# InterfazRS232Radio.net
KiCad netlist of a schematic drawn in Altium Designer
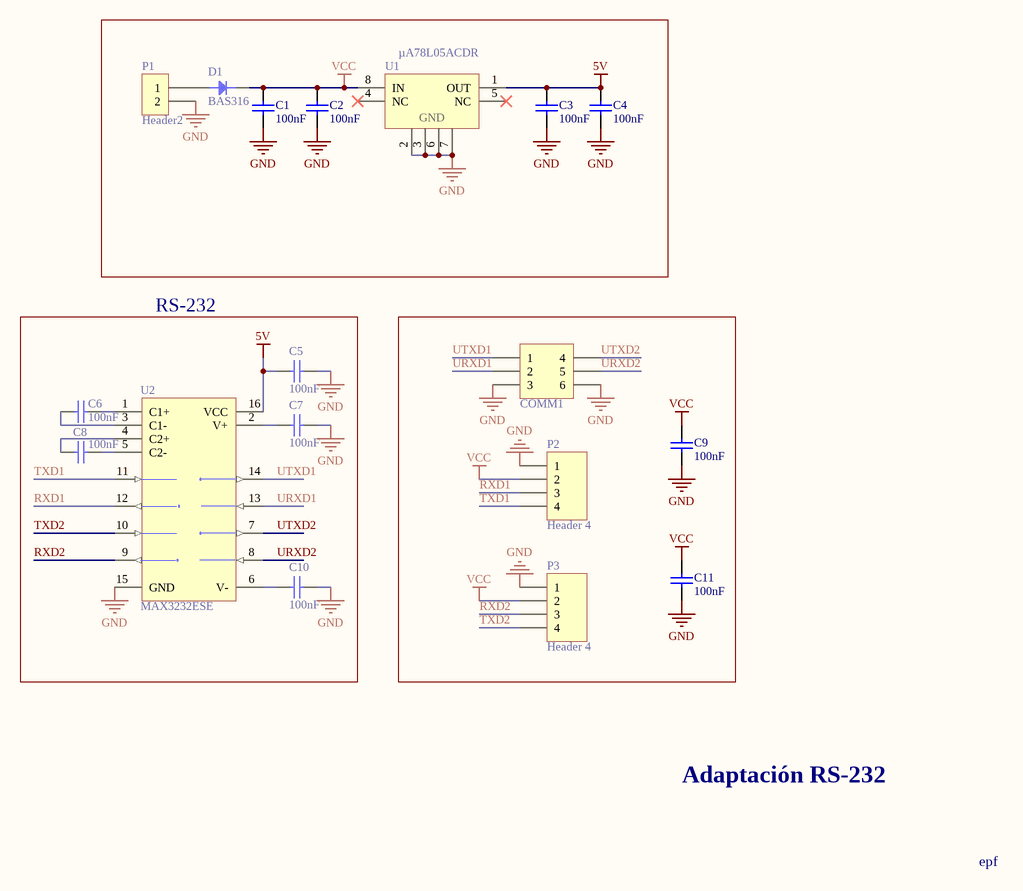
[diagram p0: InterfazRS232Radio.SchDoc]

(export (version "E")
  (design (tool "Eeschema 10.0.6"))
  (components
    (comp (ref "C1")
      (value "100nF")
      (footprint "0805_CAP")
      (fields (field (name "Comment") "Capacitor"))
      (libsource (lib "epf") (part "Cap"))
    )
    (comp (ref "C2")
      (value "100nF")
      (footprint "0805_CAP")
      (fields (field (name "Comment") "Capacitor"))
      (libsource (lib "epf") (part "Cap"))
    )
    (comp (ref "C3")
      (value "100nF")
      (footprint "0805_CAP")
      (fields (field (name "Comment") "Capacitor"))
      (libsource (lib "epf") (part "Cap"))
    )
    (comp (ref "C4")
      (value "100nF")
      (footprint "0805_CAP")
      (fields (field (name "Comment") "Capacitor"))
      (libsource (lib "epf") (part "Cap"))
    )
    (comp (ref "C5")
      (value "100nF")
      (footprint "0805_CAP")
      (fields (field (name "Comment") "Capacitor"))
      (libsource (lib "epf") (part "Cap"))
    )
    (comp (ref "C6")
      (value "100nF")
      (footprint "0805_CAP")
      (fields (field (name "Comment") "Capacitor"))
      (libsource (lib "epf") (part "Cap"))
    )
    (comp (ref "C7")
      (value "100nF")
      (footprint "0805_CAP")
      (fields (field (name "Comment") "Capacitor"))
      (libsource (lib "epf") (part "Cap"))
    )
    (comp (ref "C8")
      (value "100nF")
      (footprint "0805_CAP")
      (fields (field (name "Comment") "Capacitor"))
      (libsource (lib "epf") (part "Cap"))
    )
    (comp (ref "C9")
      (value "100nF")
      (footprint "0805_CAP")
      (fields (field (name "Comment") "Capacitor"))
      (libsource (lib "epf") (part "Cap"))
    )
    (comp (ref "C10")
      (value "100nF")
      (footprint "0805_CAP")
      (fields (field (name "Comment") "Capacitor"))
      (libsource (lib "epf") (part "Cap"))
    )
    (comp (ref "C11")
      (value "100nF")
      (footprint "0805_CAP")
      (fields (field (name "Comment") "Capacitor"))
      (libsource (lib "epf") (part "Cap"))
    )
    (comp (ref "COMM1")
      (value "AP_COMM")
      (footprint "HDR2X3_CEN")
      (description "Header, 3-Pin, Dual row")
      (fields (field (name "PUBLISHER") "Altium Limited"))
      (libsource (lib "epf") (part "AP_COMM"))
    )
    (comp (ref "D1") (value "BAS316") (footprint "SOD-323") (libsource (lib "epf") (part "BAS316")))
    (comp (ref "P1") (value "Header2") (footprint "Header2Macho") (libsource (lib "epf") (part "Header2")))
    (comp (ref "P2")
      (value "Header 4")
      (footprint "HDR1X4")
      (description "Header, 4-Pin")
      (fields (field (name "PUBLISHER") "Altium Limited"))
      (libsource (lib "Miscellaneous Connectors") (part "Header 4"))
    )
    (comp (ref "P3")
      (value "Header 4")
      (footprint "HDR1X4")
      (description "Header, 4-Pin")
      (fields (field (name "PUBLISHER") "Altium Limited"))
      (libsource (lib "Miscellaneous Connectors") (part "Header 4"))
    )
    (comp (ref "U1")
      (value "µA78L05ACDR")
      (footprint "D008_N")
      (description "Positive-Voltage Regulator")
      (fields (field (name "PUBLISHER") "Altium Limited"))
      (libsource (lib "TI Power Mgt Voltage Regulator") (part "µA78L05ACDR"))
    )
    (comp (ref "U2")
      (value "MAX3232ESE")
      (footprint "SOIC127P602-16BN")
      (libsource (lib "epf") (part "MAX3232ESE+"))
    )
  )
  (nets
    (net (code "1") (name "/RXD1") (class "Default")
      (node (ref "P2") (pin "3") (pinfunction "3_3") (pintype "passive"))
      (node (ref "U2") (pin "12") (pinfunction "R1OUT_12") (pintype "output"))
    )
    (net (code "2") (name "/RXD2") (class "Default")
      (node (ref "P3") (pin "3") (pinfunction "3_3") (pintype "passive"))
      (node (ref "U2") (pin "9") (pinfunction "R2OUT_9") (pintype "output"))
    )
    (net (code "3") (name "/TXD1") (class "Default")
      (node (ref "P2") (pin "4") (pinfunction "4_4") (pintype "passive"))
      (node (ref "U2") (pin "11") (pinfunction "T1IN_11") (pintype "input"))
    )
    (net (code "4") (name "/TXD2") (class "Default")
      (node (ref "P3") (pin "4") (pinfunction "4_4") (pintype "passive"))
      (node (ref "U2") (pin "10") (pinfunction "T2IN_10") (pintype "input"))
    )
    (net (code "5") (name "/URXD1") (class "Default")
      (node (ref "COMM1") (pin "2") (pinfunction "2_2") (pintype "passive"))
      (node (ref "U2") (pin "13") (pinfunction "R1IN_13") (pintype "input"))
    )
    (net (code "6") (name "/URXD2") (class "Default")
      (node (ref "COMM1") (pin "5") (pinfunction "5_5") (pintype "passive"))
      (node (ref "U2") (pin "8") (pinfunction "R2IN_8") (pintype "input"))
    )
    (net (code "7") (name "/UTXD1") (class "Default")
      (node (ref "COMM1") (pin "1") (pinfunction "1_1") (pintype "passive"))
      (node (ref "U2") (pin "14") (pinfunction "T1OUT_14") (pintype "output"))
    )
    (net (code "8") (name "/UTXD2") (class "Default")
      (node (ref "COMM1") (pin "4") (pinfunction "4_4") (pintype "passive"))
      (node (ref "U2") (pin "7") (pinfunction "T2OUT_7") (pintype "output"))
    )
    (net (code "9") (name "5V") (class "Default")
      (node (ref "C3") (pin "1") (pinfunction "1_1") (pintype "passive"))
      (node (ref "C4") (pin "1") (pinfunction "1_1") (pintype "passive"))
      (node (ref "C5") (pin "2") (pinfunction "2_2") (pintype "passive"))
      (node (ref "U1") (pin "1") (pinfunction "OUT_1") (pintype "power_in"))
      (node (ref "U2") (pin "16") (pinfunction "VCC_16") (pintype "power_in"))
    )
    (net (code "10") (name "GND") (class "Default")
      (node (ref "C1") (pin "2") (pinfunction "2_2") (pintype "passive"))
      (node (ref "C10") (pin "1") (pinfunction "1_1") (pintype "passive"))
      (node (ref "C11") (pin "2") (pinfunction "2_2") (pintype "passive"))
      (node (ref "C2") (pin "2") (pinfunction "2_2") (pintype "passive"))
      (node (ref "C3") (pin "2") (pinfunction "2_2") (pintype "passive"))
      (node (ref "C4") (pin "2") (pinfunction "2_2") (pintype "passive"))
      (node (ref "C5") (pin "1") (pinfunction "1_1") (pintype "passive"))
      (node (ref "C7") (pin "1") (pinfunction "1_1") (pintype "passive"))
      (node (ref "C9") (pin "2") (pinfunction "2_2") (pintype "passive"))
      (node (ref "COMM1") (pin "3") (pinfunction "3_3") (pintype "passive"))
      (node (ref "COMM1") (pin "6") (pinfunction "6_6") (pintype "passive"))
      (node (ref "P1") (pin "2") (pinfunction "2_2") (pintype "passive"))
      (node (ref "P2") (pin "1") (pinfunction "1_1") (pintype "passive"))
      (node (ref "P3") (pin "1") (pinfunction "1_1") (pintype "passive"))
      (node (ref "U1") (pin "2") (pinfunction "GND_2") (pintype "power_in"))
      (node (ref "U1") (pin "3") (pinfunction "GND_3") (pintype "power_in"))
      (node (ref "U1") (pin "6") (pinfunction "GND_6") (pintype "power_in"))
      (node (ref "U1") (pin "7") (pinfunction "GND_7") (pintype "power_in"))
      (node (ref "U2") (pin "15") (pinfunction "GND_15") (pintype "power_in"))
    )
    (net (code "11") (name "Net-(D1-A)") (class "Default")
      (node (ref "D1") (pin "2") (pinfunction "A_2") (pintype "passive"))
      (node (ref "P1") (pin "1") (pinfunction "1_1") (pintype "passive"))
    )
    (net (code "12") (name "Net-(U2-C1+)") (class "Default")
      (node (ref "C6") (pin "1") (pinfunction "1_1") (pintype "passive"))
      (node (ref "U2") (pin "1") (pinfunction "C1+_1") (pintype "passive"))
    )
    (net (code "13") (name "Net-(U2-C1-)") (class "Default")
      (node (ref "C6") (pin "2") (pinfunction "2_2") (pintype "passive"))
      (node (ref "U2") (pin "3") (pinfunction "C1-_3") (pintype "passive"))
    )
    (net (code "14") (name "Net-(U2-C2+)") (class "Default")
      (node (ref "C8") (pin "2") (pinfunction "2_2") (pintype "passive"))
      (node (ref "U2") (pin "4") (pinfunction "C2+_4") (pintype "passive"))
    )
    (net (code "15") (name "Net-(U2-C2-)") (class "Default")
      (node (ref "C8") (pin "1") (pinfunction "1_1") (pintype "passive"))
      (node (ref "U2") (pin "5") (pinfunction "C2-_5") (pintype "passive"))
    )
    (net (code "16") (name "Net-(U2-V+)") (class "Default")
      (node (ref "C7") (pin "2") (pinfunction "2_2") (pintype "passive"))
      (node (ref "U2") (pin "2") (pinfunction "V+_2") (pintype "power_in"))
    )
    (net (code "17") (name "Net-(U2-V-)") (class "Default")
      (node (ref "C10") (pin "2") (pinfunction "2_2") (pintype "passive"))
      (node (ref "U2") (pin "6") (pinfunction "V-_6") (pintype "power_in"))
    )
    (net (code "18") (name "VCC") (class "Default")
      (node (ref "C1") (pin "1") (pinfunction "1_1") (pintype "passive"))
      (node (ref "C11") (pin "1") (pinfunction "1_1") (pintype "passive"))
      (node (ref "C2") (pin "1") (pinfunction "1_1") (pintype "passive"))
      (node (ref "C9") (pin "1") (pinfunction "1_1") (pintype "passive"))
      (node (ref "D1") (pin "1") (pinfunction "K_1") (pintype "passive"))
      (node (ref "P2") (pin "2") (pinfunction "2_2") (pintype "passive"))
      (node (ref "P3") (pin "2") (pinfunction "2_2") (pintype "passive"))
      (node (ref "U1") (pin "8") (pinfunction "IN_8") (pintype "power_in"))
    )
    (net (code "19") (name "unconnected-(U1-NC-Pad4)") (class "Default")
      (node (ref "U1") (pin "4") (pinfunction "NC_4") (pintype "passive+no_connect"))
    )
    (net (code "20") (name "unconnected-(U1-NC-Pad5)") (class "Default")
      (node (ref "U1") (pin "5") (pinfunction "NC_5") (pintype "passive+no_connect"))
    )
  )
)
